# 612_jetracer_esp32s3_030008.net
KiCad netlist of a schematic drawn in EAGLE
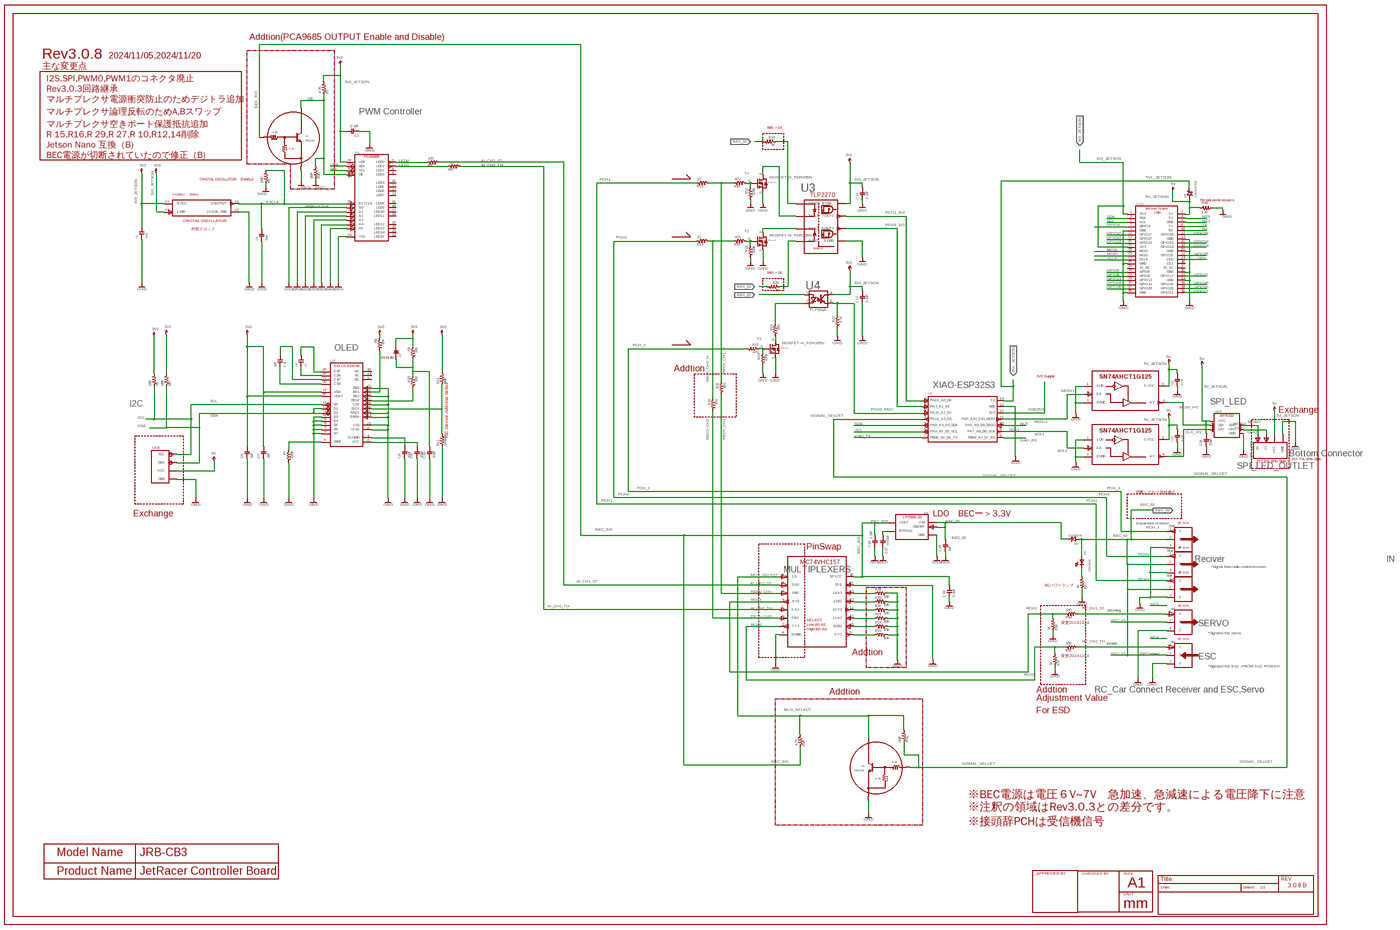
[diagram p0: schematic, sheet 1, overview]
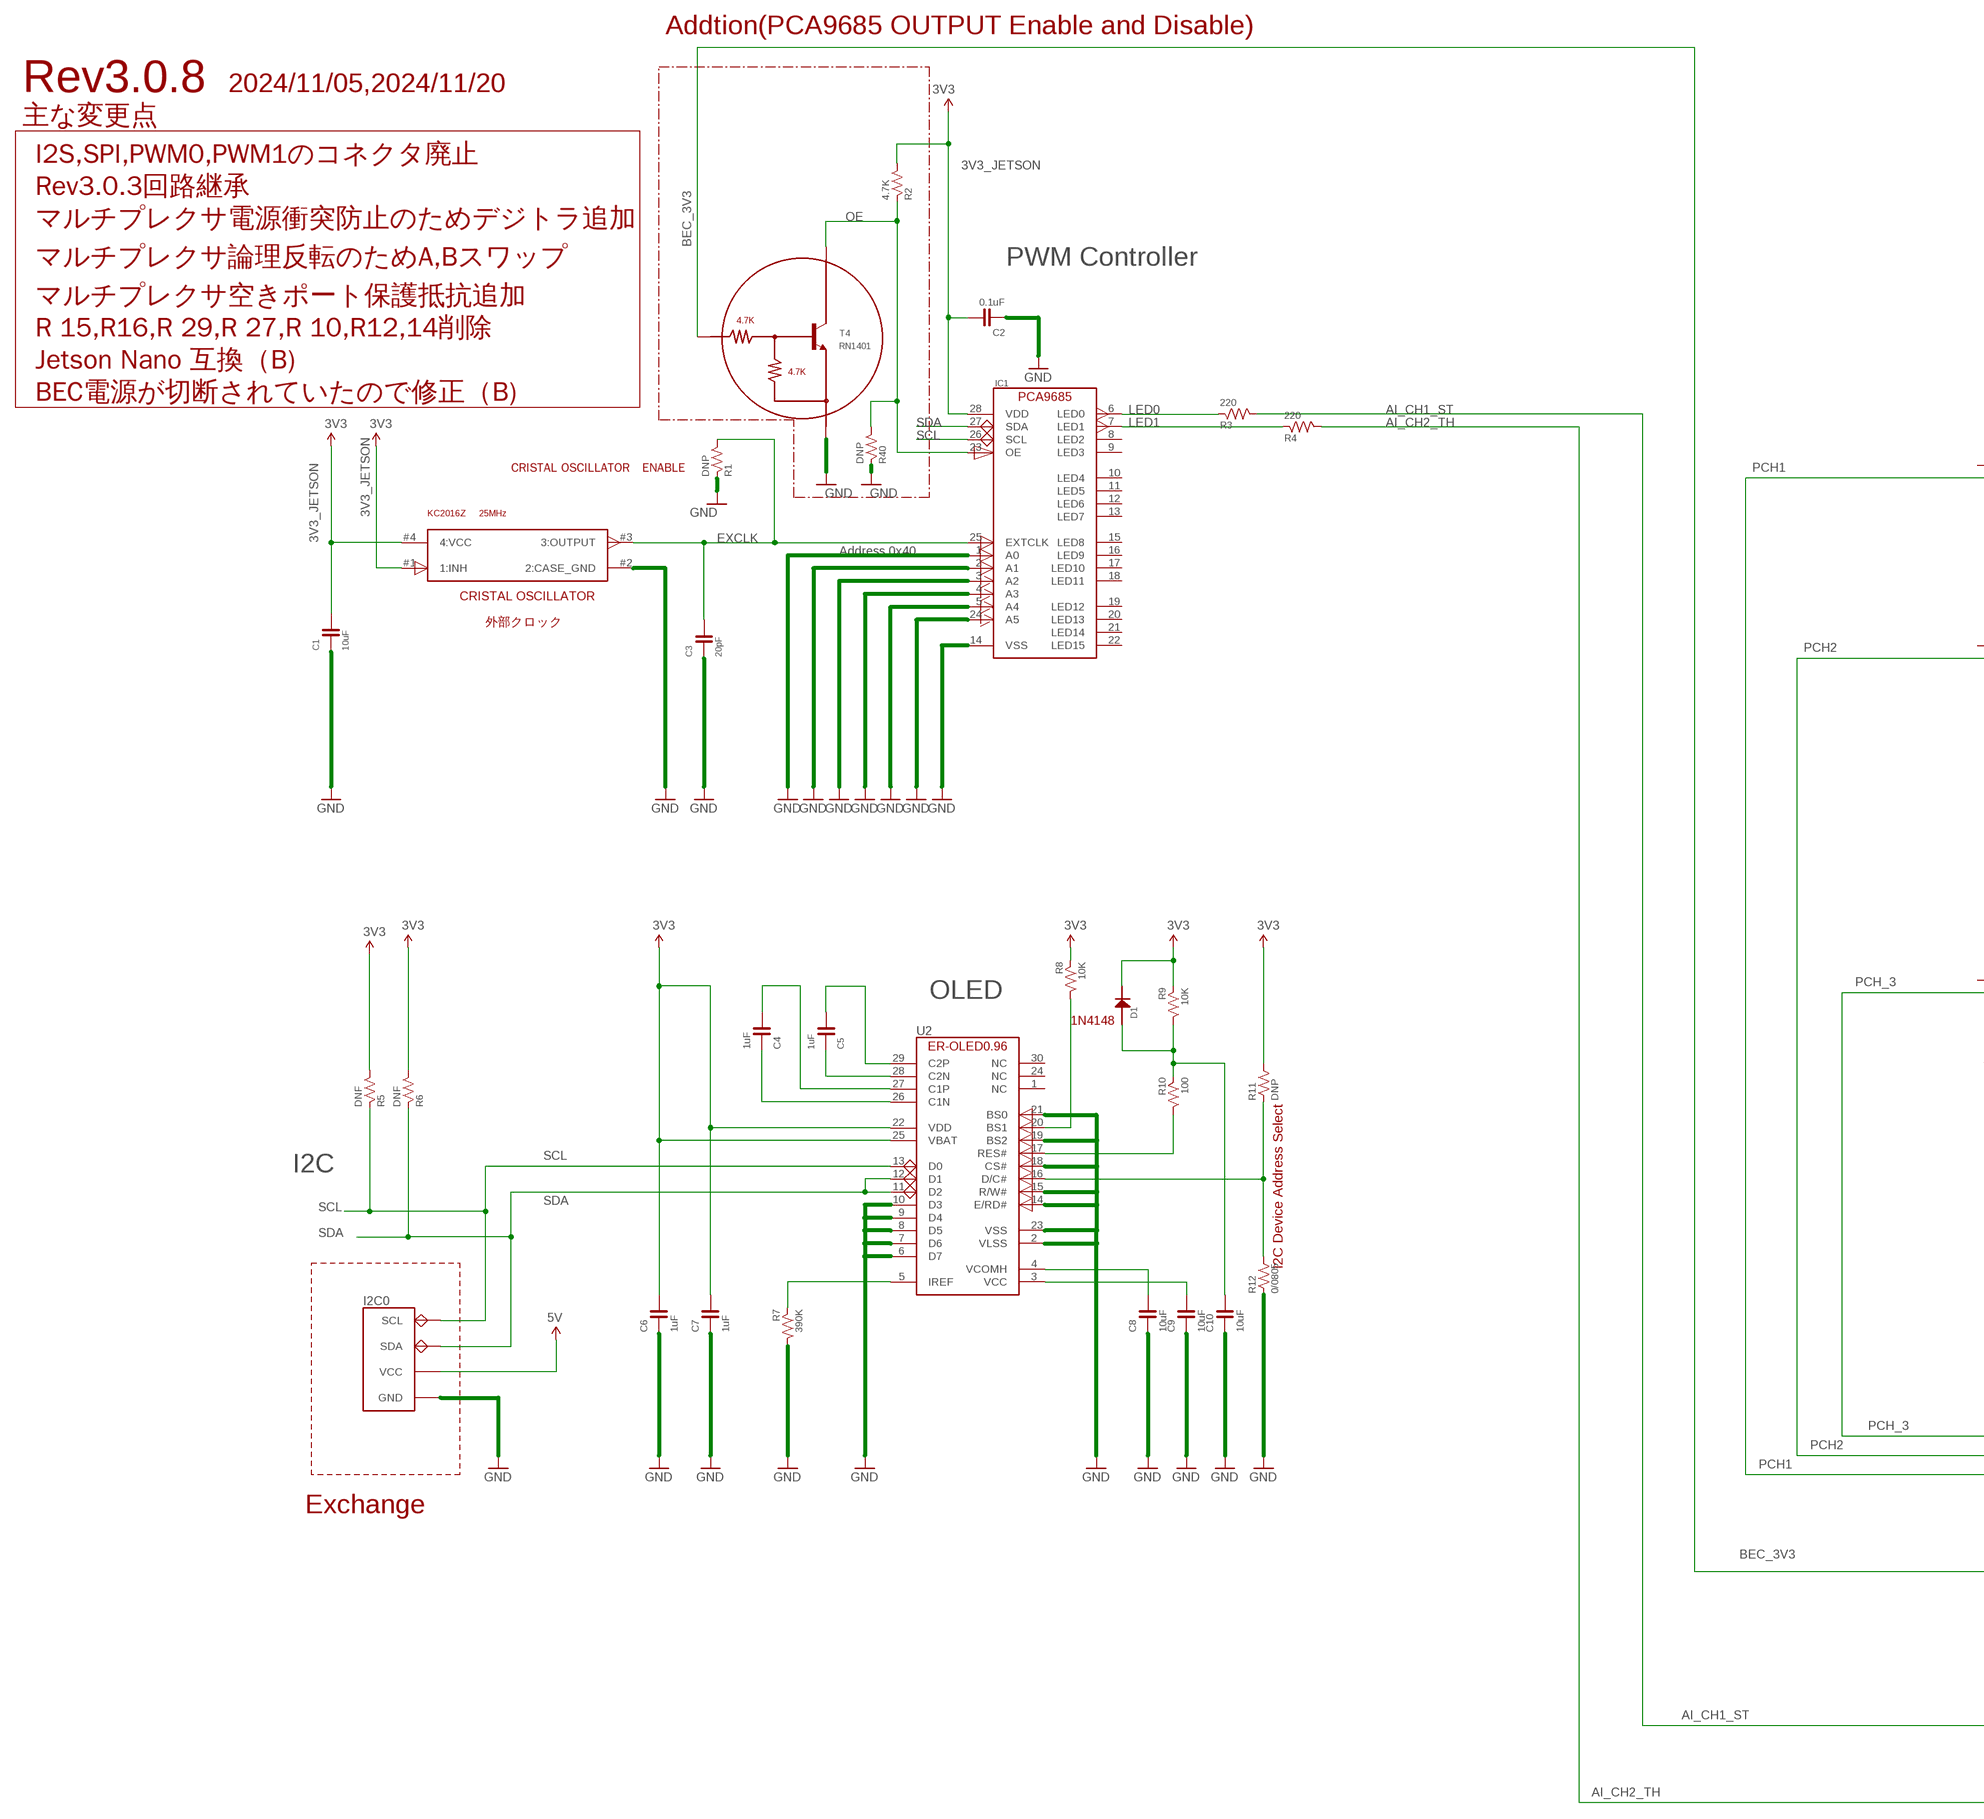
[diagram p1: schematic, sheet 1, part 1 of 4]
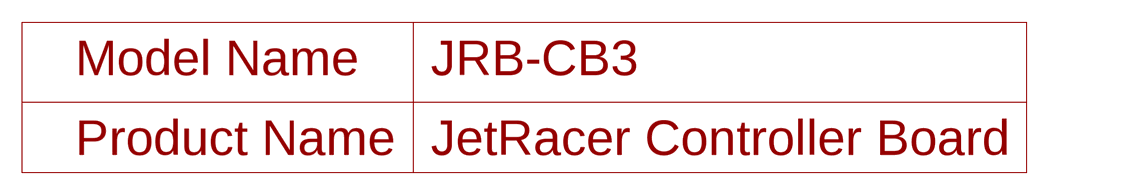
[diagram p2: schematic, sheet 1, part 2 of 4]
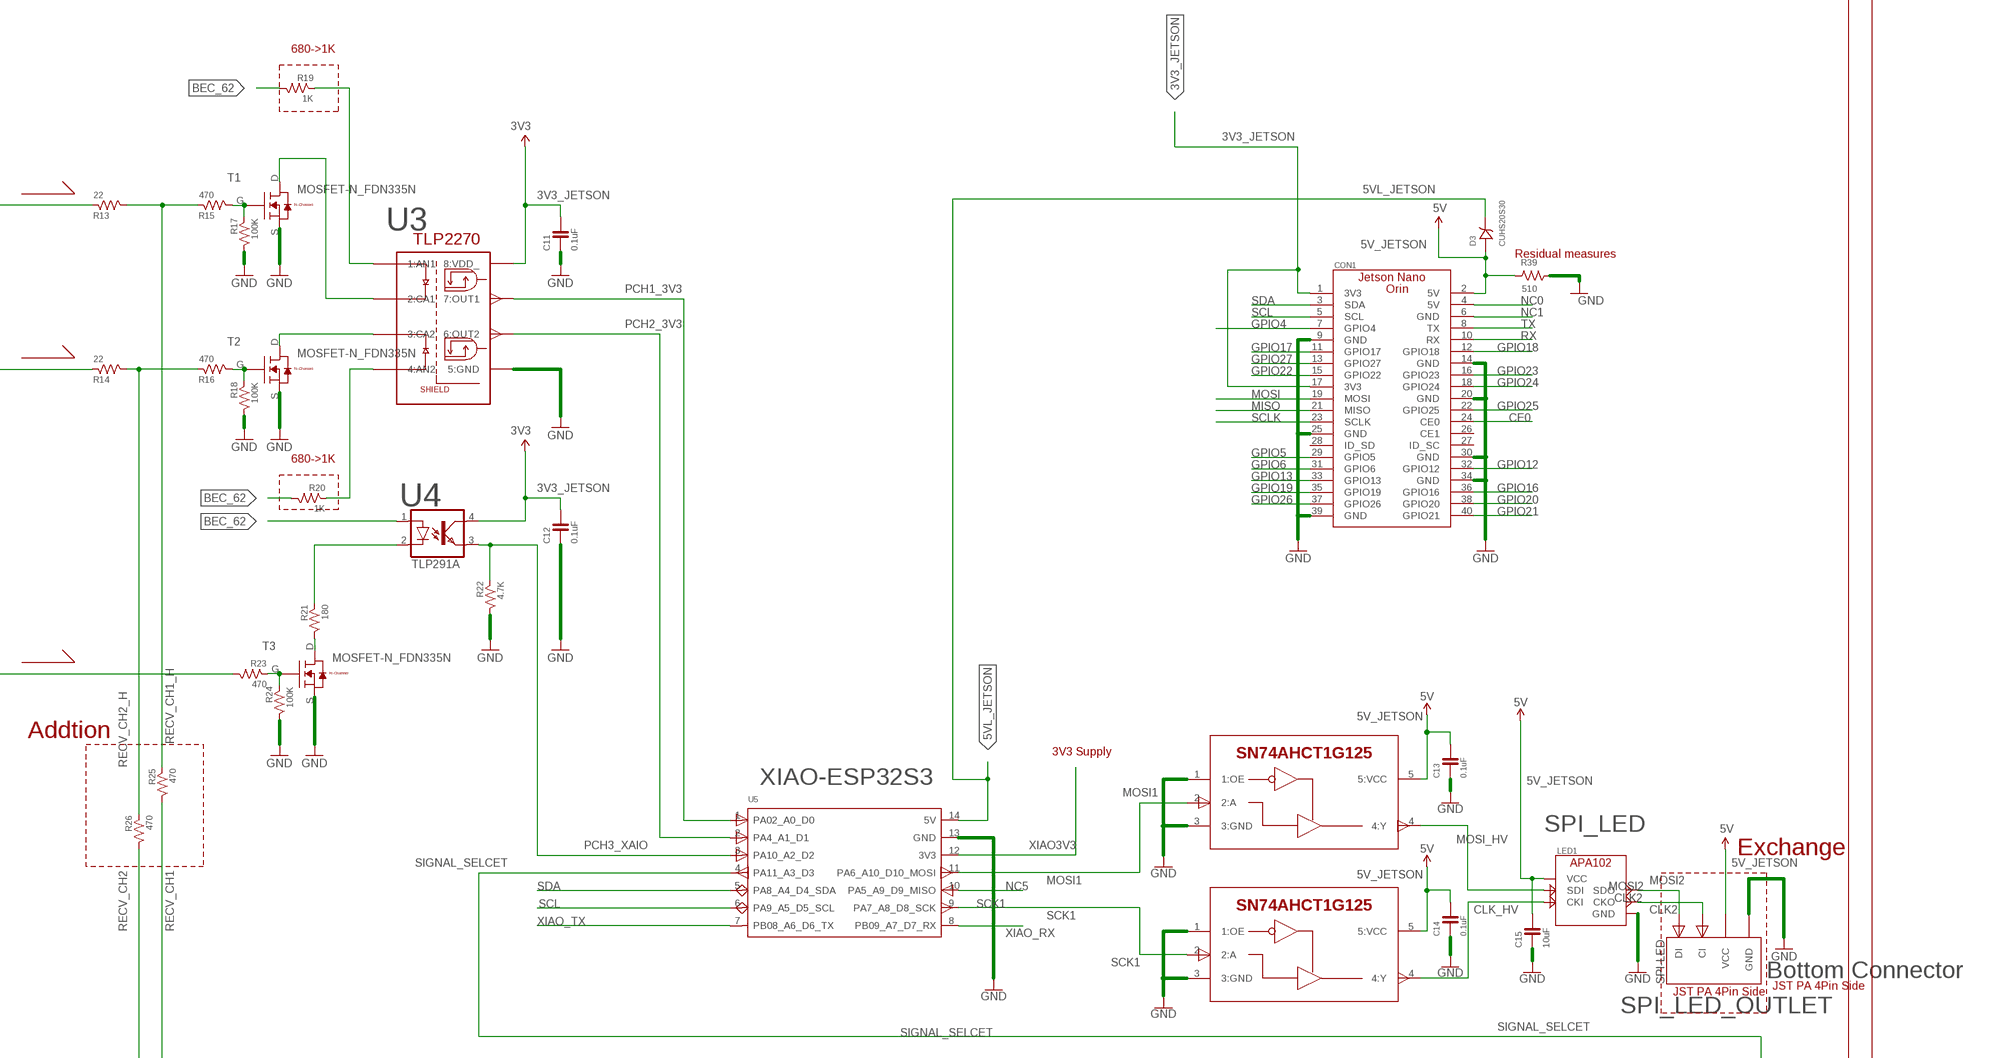
[diagram p3: schematic, sheet 1, part 3 of 4]
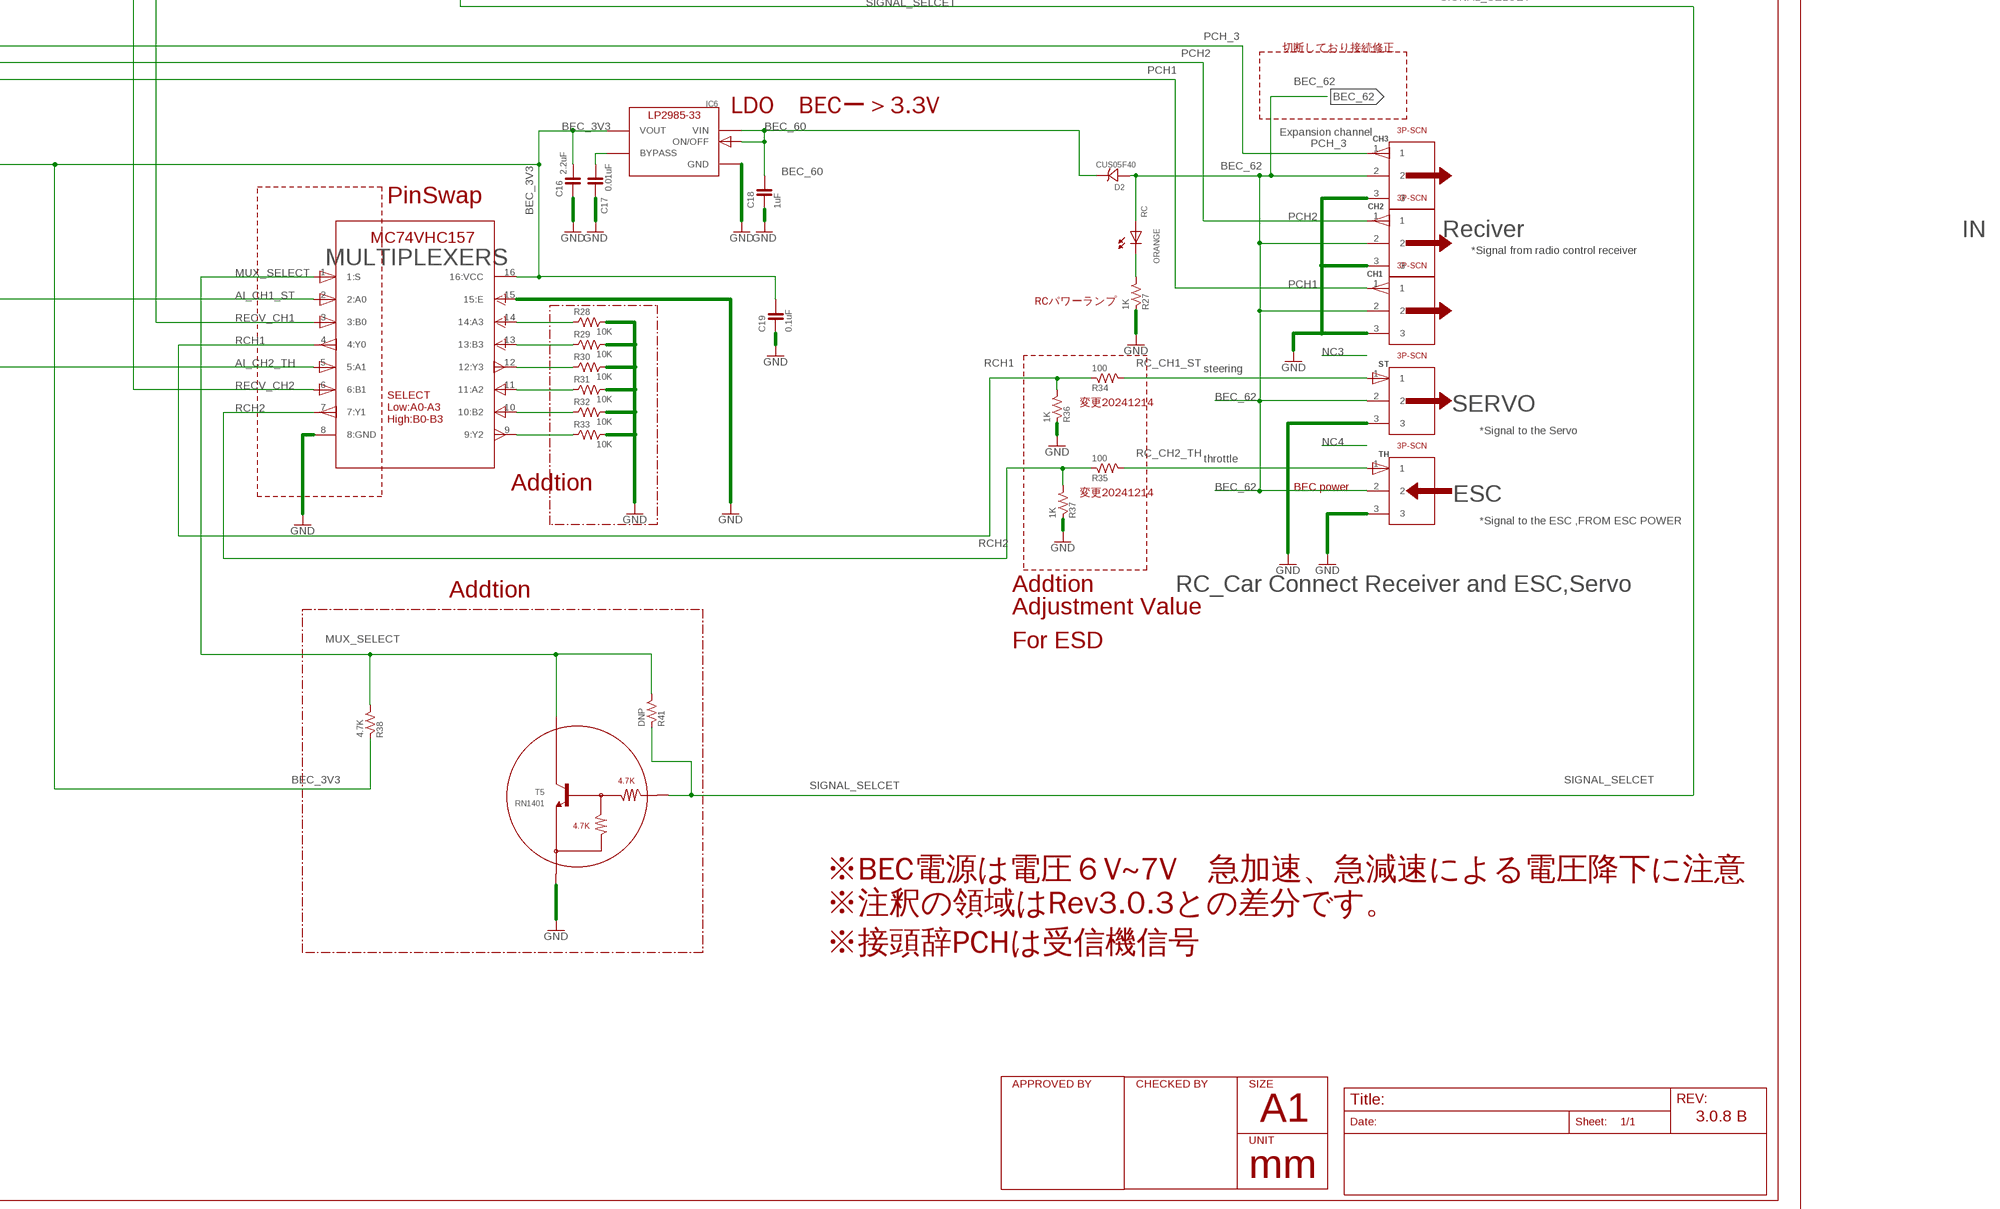
[diagram p4: schematic, sheet 1, part 4 of 4]

(export (version "E")
  (design (tool "Eeschema 10.0.6"))
  (components
    (comp (ref "C1")
      (value "10uF")
      (footprint "eagle-import:0402")
      (libsource (lib "eagle-import") (part "CAPACITOR-0402"))
    )
    (comp (ref "C2")
      (value "0.1uF")
      (footprint "eagle-import:0603")
      (libsource (lib "eagle-import") (part "CAPACITOR-0603"))
    )
    (comp (ref "C3")
      (value "20pF")
      (footprint "eagle-import:0402")
      (libsource (lib "eagle-import") (part "CAPACITOR-0402"))
    )
    (comp (ref "C4")
      (value "1uF")
      (footprint "eagle-import:0603")
      (libsource (lib "eagle-import") (part "CAPACITOR-0603"))
    )
    (comp (ref "C5")
      (value "1uF")
      (footprint "eagle-import:0603")
      (libsource (lib "eagle-import") (part "CAPACITOR-0603"))
    )
    (comp (ref "C6")
      (value "1uF")
      (footprint "eagle-import:0603")
      (libsource (lib "eagle-import") (part "CAPACITOR-0603"))
    )
    (comp (ref "C7")
      (value "1uF")
      (footprint "eagle-import:0603")
      (libsource (lib "eagle-import") (part "CAPACITOR-0603"))
    )
    (comp (ref "C8")
      (value "10uF")
      (footprint "eagle-import:0603")
      (libsource (lib "eagle-import") (part "CAPACITOR-0603"))
    )
    (comp (ref "C9")
      (value "10uF")
      (footprint "eagle-import:0603")
      (libsource (lib "eagle-import") (part "CAPACITOR-0603"))
    )
    (comp (ref "C10")
      (value "10uF")
      (footprint "eagle-import:0603")
      (libsource (lib "eagle-import") (part "CAPACITOR-0603"))
    )
    (comp (ref "C11")
      (value "0.1uF")
      (footprint "eagle-import:0603")
      (libsource (lib "eagle-import") (part "CAPACITOR-0603"))
    )
    (comp (ref "C12")
      (value "0.1uF")
      (footprint "eagle-import:0603")
      (libsource (lib "eagle-import") (part "CAPACITOR-0603"))
    )
    (comp (ref "C13")
      (value "0.1uF")
      (footprint "eagle-import:0402")
      (libsource (lib "eagle-import") (part "CAPACITOR-0402"))
    )
    (comp (ref "C14")
      (value "0.1uF")
      (footprint "eagle-import:0402")
      (libsource (lib "eagle-import") (part "CAPACITOR-0402"))
    )
    (comp (ref "C15")
      (value "10uF")
      (footprint "eagle-import:0603")
      (libsource (lib "eagle-import") (part "CAPACITOR-0603"))
    )
    (comp (ref "C16")
      (value "2.2uF")
      (footprint "eagle-import:0603")
      (libsource (lib "eagle-import") (part "CAPACITOR-0603"))
    )
    (comp (ref "C17")
      (value "0.01uF")
      (footprint "eagle-import:0603")
      (libsource (lib "eagle-import") (part "CAPACITOR-0603"))
    )
    (comp (ref "C18")
      (value "1uF")
      (footprint "eagle-import:0603")
      (libsource (lib "eagle-import") (part "CAPACITOR-0603"))
    )
    (comp (ref "C19")
      (value "0.1uF")
      (footprint "eagle-import:0603")
      (libsource (lib "eagle-import") (part "CAPACITOR-0603"))
    )
    (comp (ref "CH1")
      (value "3P-SCN")
      (footprint "eagle-import:3P-SCN")
      (libsource (lib "eagle-import") (part "3P-SCN"))
    )
    (comp (ref "CH2")
      (value "3P-SCN")
      (footprint "eagle-import:3P-SCN")
      (libsource (lib "eagle-import") (part "3P-SCN"))
    )
    (comp (ref "CH3")
      (value "3P-SCN")
      (footprint "eagle-import:3P-SCN")
      (libsource (lib "eagle-import") (part "3P-SCN"))
    )
    (comp (ref "CON1")
      (value "JETSON_NANOJETSON_ORIN_NANO")
      (footprint "eagle-import:JETSON_ORIN_NANO_DIMENTION")
      (libsource (lib "eagle-import") (part "JETSON_NANOJETSON_ORIN_NANO"))
    )
    (comp (ref "D1")
      (value "1N4148")
      (footprint "eagle-import:1N4148W")
      (libsource (lib "eagle-import") (part "1N4148"))
    )
    (comp (ref "D2")
      (value "CUS05F40")
      (footprint "eagle-import:CUS05F40")
      (libsource (lib "eagle-import") (part "CUS05F40"))
    )
    (comp (ref "D3")
      (value "CUHS20S30")
      (footprint "eagle-import:US2H")
      (libsource (lib "eagle-import") (part "CUHS20S30"))
    )
    (comp (ref "I2C0")
      (value "FABO_BRICK_I2C-B04B-PASK-1")
      (footprint "eagle-import:FABO_BRICK_I2C_B04B-PASK-1")
      (libsource (lib "eagle-import") (part "FABO_BRICK_I2C-B04B-PASK-1"))
    )
    (comp (ref "IC1")
      (value "PCA9685PW,BS")
      (footprint "eagle-import:PCA9685")
      (libsource (lib "eagle-import") (part "PCA9685PW,BS"))
    )
    (comp (ref "IC3")
      (value "SN74AHCT1G125")
      (footprint "eagle-import:SOT-1DOT1")
      (libsource (lib "eagle-import") (part "SN74AHCT1G125"))
    )
    (comp (ref "IC4")
      (value "SN74AHCT1G125")
      (footprint "eagle-import:SOT-1DOT1")
      (libsource (lib "eagle-import") (part "SN74AHCT1G125"))
    )
    (comp (ref "IC5")
      (value "MC74VHC157")
      (footprint "eagle-import:MC74VHC157_TSSOP-16")
      (libsource (lib "eagle-import") (part "MC74VHC157"))
    )
    (comp (ref "IC6")
      (value "LP2985-33DBVR")
      (footprint "eagle-import:SOT-23-5")
      (libsource (lib "eagle-import") (part "LP2985-33DBVR"))
    )
    (comp (ref "LED1")
      (value "APA102_IPIXEL")
      (footprint "eagle-import:APA102_2020")
      (libsource (lib "eagle-import") (part "APA102_IPIXEL"))
    )
    (comp (ref "R1")
      (value "DNP")
      (footprint "eagle-import:0603")
      (libsource (lib "eagle-import") (part "RESISTOR-0603"))
    )
    (comp (ref "R2")
      (value "4.7K")
      (footprint "eagle-import:0603")
      (libsource (lib "eagle-import") (part "RESISTOR-0603"))
    )
    (comp (ref "R3")
      (value "220")
      (footprint "eagle-import:0603")
      (libsource (lib "eagle-import") (part "RESISTOR-0603"))
    )
    (comp (ref "R4")
      (value "220")
      (footprint "eagle-import:0603")
      (libsource (lib "eagle-import") (part "RESISTOR-0603"))
    )
    (comp (ref "R5")
      (value "DNF")
      (footprint "eagle-import:0603")
      (libsource (lib "eagle-import") (part "RESISTOR-0603"))
    )
    (comp (ref "R6")
      (value "DNF")
      (footprint "eagle-import:0603")
      (libsource (lib "eagle-import") (part "RESISTOR-0603"))
    )
    (comp (ref "R7")
      (value "390K")
      (footprint "eagle-import:0603")
      (libsource (lib "eagle-import") (part "RESISTOR-0603"))
    )
    (comp (ref "R8")
      (value "10K")
      (footprint "eagle-import:0603")
      (libsource (lib "eagle-import") (part "RESISTOR-0603"))
    )
    (comp (ref "R9")
      (value "10K")
      (footprint "eagle-import:0603")
      (libsource (lib "eagle-import") (part "RESISTOR-0603"))
    )
    (comp (ref "R10")
      (value "100")
      (footprint "eagle-import:0603")
      (libsource (lib "eagle-import") (part "RESISTOR-0603"))
    )
    (comp (ref "R11")
      (value "DNP")
      (footprint "eagle-import:0805")
      (fields (field (name "SPICEPREFIX") "R"))
      (libsource (lib "eagle-import") (part "RESISTOR-0805"))
    )
    (comp (ref "R12")
      (value "0/0805")
      (footprint "eagle-import:0805")
      (libsource (lib "eagle-import") (part "RESISTOR-0805"))
    )
    (comp (ref "R13")
      (value "22")
      (footprint "eagle-import:0603")
      (libsource (lib "eagle-import") (part "RESISTOR-0603"))
    )
    (comp (ref "R14")
      (value "22")
      (footprint "eagle-import:0603")
      (fields (field (name "SPICEPREFIX") "R"))
      (libsource (lib "eagle-import") (part "RESISTOR-0603"))
    )
    (comp (ref "R15")
      (value "470")
      (footprint "eagle-import:0603")
      (libsource (lib "eagle-import") (part "RESISTOR-0603"))
    )
    (comp (ref "R16")
      (value "470")
      (footprint "eagle-import:0603")
      (libsource (lib "eagle-import") (part "RESISTOR-0603"))
    )
    (comp (ref "R17")
      (value "100K")
      (footprint "eagle-import:0603")
      (libsource (lib "eagle-import") (part "RESISTOR-0603"))
    )
    (comp (ref "R18")
      (value "100K")
      (footprint "eagle-import:0603")
      (libsource (lib "eagle-import") (part "RESISTOR-0603"))
    )
    (comp (ref "R19")
      (value "1K")
      (footprint "eagle-import:0603")
      (libsource (lib "eagle-import") (part "RESISTOR-0603"))
    )
    (comp (ref "R20")
      (value "1K")
      (footprint "eagle-import:0603")
      (libsource (lib "eagle-import") (part "RESISTOR-0603"))
    )
    (comp (ref "R21")
      (value "180")
      (footprint "eagle-import:0603")
      (libsource (lib "eagle-import") (part "RESISTOR-0603"))
    )
    (comp (ref "R22")
      (value "4.7K")
      (footprint "eagle-import:0603")
      (libsource (lib "eagle-import") (part "RESISTOR-0603"))
    )
    (comp (ref "R23")
      (value "470")
      (footprint "eagle-import:0603")
      (libsource (lib "eagle-import") (part "RESISTOR-0603"))
    )
    (comp (ref "R24")
      (value "100K")
      (footprint "eagle-import:0603")
      (libsource (lib "eagle-import") (part "RESISTOR-0603"))
    )
    (comp (ref "R25")
      (value "470")
      (footprint "eagle-import:0603")
      (libsource (lib "eagle-import") (part "RESISTOR-0603"))
    )
    (comp (ref "R26")
      (value "470")
      (footprint "eagle-import:0603")
      (libsource (lib "eagle-import") (part "RESISTOR-0603"))
    )
    (comp (ref "R27")
      (value "1K")
      (footprint "eagle-import:0603")
      (libsource (lib "eagle-import") (part "RESISTOR-0603"))
    )
    (comp (ref "R28")
      (value "10K")
      (footprint "eagle-import:0402")
      (fields (field (name "SPICEPREFIX") "R"))
      (libsource (lib "eagle-import") (part "RESISTOR-0402"))
    )
    (comp (ref "R29")
      (value "10K")
      (footprint "eagle-import:0402")
      (libsource (lib "eagle-import") (part "RESISTOR-0402"))
    )
    (comp (ref "R30")
      (value "10K")
      (footprint "eagle-import:0402")
      (fields (field (name "SPICEPREFIX") "R"))
      (libsource (lib "eagle-import") (part "RESISTOR-0402"))
    )
    (comp (ref "R31")
      (value "10K")
      (footprint "eagle-import:0402")
      (libsource (lib "eagle-import") (part "RESISTOR-0402"))
    )
    (comp (ref "R32")
      (value "10K")
      (footprint "eagle-import:0402")
      (libsource (lib "eagle-import") (part "RESISTOR-0402"))
    )
    (comp (ref "R33")
      (value "10K")
      (footprint "eagle-import:0402")
      (libsource (lib "eagle-import") (part "RESISTOR-0402"))
    )
    (comp (ref "R34")
      (value "100")
      (footprint "eagle-import:0603")
      (libsource (lib "eagle-import") (part "RESISTOR-0603"))
    )
    (comp (ref "R35")
      (value "100")
      (footprint "eagle-import:0603")
      (libsource (lib "eagle-import") (part "RESISTOR-0603"))
    )
    (comp (ref "R36")
      (value "1K")
      (footprint "eagle-import:0603")
      (libsource (lib "eagle-import") (part "RESISTOR-0603"))
    )
    (comp (ref "R37")
      (value "1K")
      (footprint "eagle-import:0603")
      (libsource (lib "eagle-import") (part "RESISTOR-0603"))
    )
    (comp (ref "R38")
      (value "4.7K")
      (footprint "eagle-import:0603")
      (libsource (lib "eagle-import") (part "RESISTOR-0603"))
    )
    (comp (ref "R39")
      (value "510")
      (footprint "eagle-import:0805")
      (libsource (lib "eagle-import") (part "RESISTOR-0805"))
    )
    (comp (ref "R40")
      (value "DNP")
      (footprint "eagle-import:0603")
      (libsource (lib "eagle-import") (part "RESISTOR-0603"))
    )
    (comp (ref "R41")
      (value "DNP")
      (footprint "eagle-import:0603")
      (libsource (lib "eagle-import") (part "RESISTOR-0603"))
    )
    (comp (ref "RC")
      (value "ORANGE")
      (footprint "eagle-import:0603")
      (libsource (lib "eagle-import") (part "LED-0603"))
    )
    (comp (ref "SPI-LED")
      (value "FABO-SPI-LED-B04B")
      (footprint "eagle-import:SPI-B04B-PASK-1")
      (libsource (lib "eagle-import") (part "FABO-SPI-LED-B04B"))
    )
    (comp (ref "ST")
      (value "3P-SCN")
      (footprint "eagle-import:3P-SCN")
      (libsource (lib "eagle-import") (part "3P-SCN"))
    )
    (comp (ref "T1")
      (value "MOSFET-N_FDN335N")
      (footprint "eagle-import:SUPERSOT-3")
      (libsource (lib "eagle-import") (part "MOSFET-N_FDN335N"))
    )
    (comp (ref "T2")
      (value "MOSFET-N_FDN335N")
      (footprint "eagle-import:SUPERSOT-3")
      (libsource (lib "eagle-import") (part "MOSFET-N_FDN335N"))
    )
    (comp (ref "T3")
      (value "MOSFET-N_FDN335N")
      (footprint "eagle-import:SUPERSOT-3")
      (libsource (lib "eagle-import") (part "MOSFET-N_FDN335N"))
    )
    (comp (ref "T4")
      (value "RN1401")
      (footprint "eagle-import:SC-59")
      (libsource (lib "eagle-import") (part "RN1401"))
    )
    (comp (ref "T5")
      (value "RN1401")
      (footprint "eagle-import:SC-59")
      (libsource (lib "eagle-import") (part "RN1401"))
    )
    (comp (ref "TH")
      (value "3P-SCN")
      (footprint "eagle-import:3P-SCN")
      (libsource (lib "eagle-import") (part "3P-SCN"))
    )
    (comp (ref "U1")
      (value "KC2016Z")
      (footprint "eagle-import:KC2016Z")
      (fields (field (name "SPICEPREFIX") "E"))
      (libsource (lib "eagle-import") (part "KC2016Z"))
    )
    (comp (ref "U2")
      (value "ER-OLED0.96-1ER-CON30HT-1")
      (footprint "eagle-import:ER-CON30HT-1")
      (libsource (lib "eagle-import") (part "ER-OLED0.96-1ER-CON30HT-1"))
    )
    (comp (ref "U3")
      (value "TLP2270")
      (footprint "eagle-import:TLP2270")
      (libsource (lib "eagle-import") (part "TLP2270"))
    )
    (comp (ref "U4")
      (value "TLP291A")
      (footprint "eagle-import:11-3C1")
      (libsource (lib "eagle-import") (part "TLP291A"))
    )
    (comp (ref "U5")
      (value "MOUDLE-SEEEDUINO-XIAO-ESP32C3SINGLESIDE")
      (footprint "eagle-import:MOUDLE14P-DIP_SINGLE")
      (libsource (lib "eagle-import") (part "MOUDLE-SEEEDUINO-XIAO-ESP32C3SINGLESIDE"))
    )
  )
  (nets
    (net (code "1") (name "/AI_CH1_ST") (class "Default")
      (node (ref "IC5") (pin "2") (pinfunction "2:A0_2") (pintype "bidirectional"))
      (node (ref "R3") (pin "2") (pinfunction "2_2") (pintype "bidirectional"))
    )
    (net (code "2") (name "/AI_CH2_TH") (class "Default")
      (node (ref "IC5") (pin "5") (pinfunction "5:A1_5") (pintype "bidirectional"))
      (node (ref "R4") (pin "2") (pinfunction "2_2") (pintype "bidirectional"))
    )
    (net (code "3") (name "/BEC_3V3") (class "Default")
      (node (ref "C16") (pin "2") (pinfunction "2_2") (pintype "passive"))
      (node (ref "C19") (pin "2") (pinfunction "2_2") (pintype "passive"))
      (node (ref "IC5") (pin "16") (pinfunction "16:VCC_16") (pintype "bidirectional"))
      (node (ref "IC6") (pin "5") (pinfunction "VOUT_5") (pintype "output"))
      (node (ref "R38") (pin "1") (pinfunction "1_1") (pintype "bidirectional"))
      (node (ref "T4") (pin "B") (pinfunction "B_B") (pintype "passive"))
    )
    (net (code "4") (name "/BEC_60") (class "Default")
      (node (ref "C18") (pin "2") (pinfunction "2_2") (pintype "passive"))
      (node (ref "D2") (pin "C") (pinfunction "CATHODE_C") (pintype "bidirectional"))
      (node (ref "IC6") (pin "1") (pinfunction "VIN_1") (pintype "input"))
      (node (ref "IC6") (pin "3") (pinfunction "ON/OFF_3") (pintype "input"))
    )
    (net (code "5") (name "/CE0") (class "Default")
      (node (ref "CON1") (pin "24") (pinfunction "CE0_24") (pintype "bidirectional"))
    )
    (net (code "6") (name "/CLK2") (class "Default")
      (node (ref "LED1") (pin "CKO") (pinfunction "CKO_CKO") (pintype "bidirectional"))
      (node (ref "SPI-LED") (pin "CI") (pinfunction "CI_CI") (pintype "bidirectional"))
    )
    (net (code "7") (name "/CLK_HV") (class "Default")
      (node (ref "IC4") (pin "4") (pinfunction "4:Y_4") (pintype "output"))
      (node (ref "LED1") (pin "CKI") (pinfunction "CKI_CKI") (pintype "bidirectional"))
    )
    (net (code "8") (name "/EXCLK") (class "Default")
      (node (ref "C3") (pin "2") (pinfunction "2_2") (pintype "passive"))
      (node (ref "IC1") (pin "25") (pinfunction "EXTCLK_25") (pintype "bidirectional"))
      (node (ref "R1") (pin "2") (pinfunction "2_2") (pintype "bidirectional"))
      (node (ref "U1") (pin "#3") (pinfunction "3:OUTPUT_#3") (pintype "bidirectional"))
    )
    (net (code "9") (name "/GPIO4") (class "Default")
      (node (ref "CON1") (pin "7") (pinfunction "GPIO4_7") (pintype "bidirectional"))
    )
    (net (code "10") (name "/GPIO5") (class "Default")
      (node (ref "CON1") (pin "29") (pinfunction "GPIO5_29") (pintype "bidirectional"))
    )
    (net (code "11") (name "/GPIO6") (class "Default")
      (node (ref "CON1") (pin "31") (pinfunction "GPIO6_31") (pintype "bidirectional"))
    )
    (net (code "12") (name "/GPIO12") (class "Default")
      (node (ref "CON1") (pin "32") (pinfunction "GPIO12_32") (pintype "bidirectional"))
    )
    (net (code "13") (name "/GPIO13") (class "Default")
      (node (ref "CON1") (pin "33") (pinfunction "GPIO13_33") (pintype "bidirectional"))
    )
    (net (code "14") (name "/GPIO16") (class "Default")
      (node (ref "CON1") (pin "36") (pinfunction "GPIO16_36") (pintype "bidirectional"))
    )
    (net (code "15") (name "/GPIO17") (class "Default")
      (node (ref "CON1") (pin "11") (pinfunction "GPIO17_11") (pintype "bidirectional"))
    )
    (net (code "16") (name "/GPIO18") (class "Default")
      (node (ref "CON1") (pin "12") (pinfunction "GPIO18_12") (pintype "bidirectional"))
    )
    (net (code "17") (name "/GPIO19") (class "Default")
      (node (ref "CON1") (pin "35") (pinfunction "GPIO19_35") (pintype "bidirectional"))
    )
    (net (code "18") (name "/GPIO20") (class "Default")
      (node (ref "CON1") (pin "38") (pinfunction "GPIO20_38") (pintype "bidirectional"))
    )
    (net (code "19") (name "/GPIO21") (class "Default")
      (node (ref "CON1") (pin "40") (pinfunction "GPIO21_40") (pintype "bidirectional"))
    )
    (net (code "20") (name "/GPIO22") (class "Default")
      (node (ref "CON1") (pin "15") (pinfunction "GPIO22_15") (pintype "bidirectional"))
    )
    (net (code "21") (name "/GPIO23") (class "Default")
      (node (ref "CON1") (pin "16") (pinfunction "GPIO23_16") (pintype "bidirectional"))
    )
    (net (code "22") (name "/GPIO24") (class "Default")
      (node (ref "CON1") (pin "18") (pinfunction "GPIO24_18") (pintype "bidirectional"))
    )
    (net (code "23") (name "/GPIO25") (class "Default")
      (node (ref "CON1") (pin "22") (pinfunction "GPIO25_22") (pintype "bidirectional"))
    )
    (net (code "24") (name "/GPIO26") (class "Default")
      (node (ref "CON1") (pin "37") (pinfunction "GPIO26_37") (pintype "bidirectional"))
    )
    (net (code "25") (name "/GPIO27") (class "Default")
      (node (ref "CON1") (pin "13") (pinfunction "GPIO27_13") (pintype "bidirectional"))
    )
    (net (code "26") (name "/LED0") (class "Default")
      (node (ref "IC1") (pin "6") (pinfunction "LED0_6") (pintype "bidirectional"))
      (node (ref "R3") (pin "1") (pinfunction "1_1") (pintype "bidirectional"))
    )
    (net (code "27") (name "/LED1") (class "Default")
      (node (ref "IC1") (pin "7") (pinfunction "LED1_7") (pintype "bidirectional"))
      (node (ref "R4") (pin "1") (pinfunction "1_1") (pintype "bidirectional"))
    )
    (net (code "28") (name "/MISO") (class "Default")
      (node (ref "CON1") (pin "21") (pinfunction "MISO_21") (pintype "bidirectional"))
    )
    (net (code "29") (name "/MOSI") (class "Default")
      (node (ref "CON1") (pin "19") (pinfunction "MOSI_19") (pintype "bidirectional"))
    )
    (net (code "30") (name "/MOSI1") (class "Default")
      (node (ref "IC3") (pin "2") (pinfunction "2:A_2") (pintype "input"))
      (node (ref "U5") (pin "11") (pinfunction "PA6_A10_D10_MOSI_11") (pintype "bidirectional"))
    )
    (net (code "31") (name "/MOSI2") (class "Default")
      (node (ref "LED1") (pin "SDO") (pinfunction "SDO_SDO") (pintype "bidirectional"))
      (node (ref "SPI-LED") (pin "DI") (pinfunction "DI_DI") (pintype "bidirectional"))
    )
    (net (code "32") (name "/MOSI_HV") (class "Default")
      (node (ref "IC3") (pin "4") (pinfunction "4:Y_4") (pintype "output"))
      (node (ref "LED1") (pin "SDI") (pinfunction "SDI_SDI") (pintype "bidirectional"))
    )
    (net (code "33") (name "/MUX_SELECT") (class "Default")
      (node (ref "IC5") (pin "1") (pinfunction "1:S_1") (pintype "bidirectional"))
      (node (ref "R38") (pin "2") (pinfunction "2_2") (pintype "bidirectional"))
      (node (ref "R41") (pin "2") (pinfunction "2_2") (pintype "bidirectional"))
      (node (ref "T5") (pin "C") (pinfunction "C_C") (pintype "passive"))
    )
    (net (code "34") (name "/NC0") (class "Default")
      (node (ref "CON1") (pin "4") (pinfunction "5V_4") (pintype "bidirectional"))
    )
    (net (code "35") (name "/NC1") (class "Default")
      (node (ref "CON1") (pin "6") (pinfunction "GND_6") (pintype "bidirectional"))
    )
    (net (code "38") (name "/NC5") (class "Default")
      (node (ref "U5") (pin "10") (pinfunction "PA5_A9_D9_MISO_10") (pintype "bidirectional"))
    )
    (net (code "39") (name "/OE") (class "Default")
      (node (ref "IC1") (pin "23") (pinfunction "OE_23") (pintype "bidirectional"))
      (node (ref "R2") (pin "1") (pinfunction "1_1") (pintype "bidirectional"))
      (node (ref "R40") (pin "2") (pinfunction "2_2") (pintype "bidirectional"))
      (node (ref "T4") (pin "C") (pinfunction "C_C") (pintype "passive"))
    )
    (net (code "40") (name "/PCH1") (class "Default")
      (node (ref "CH1") (pin "1") (pinfunction "1_1") (pintype "bidirectional"))
      (node (ref "R13") (pin "1") (pinfunction "1_1") (pintype "bidirectional"))
    )
    (net (code "41") (name "/PCH1_3V3") (class "Default")
      (node (ref "U3") (pin "7") (pinfunction "7:OUT1_7") (pintype "bidirectional"))
      (node (ref "U5") (pin "1") (pinfunction "PA02_A0_D0_1") (pintype "bidirectional"))
    )
    (net (code "42") (name "/PCH2") (class "Default")
      (node (ref "CH2") (pin "1") (pinfunction "1_1") (pintype "bidirectional"))
      (node (ref "R14") (pin "1") (pinfunction "1_1") (pintype "bidirectional"))
    )
    (net (code "43") (name "/PCH2_3V3") (class "Default")
      (node (ref "U3") (pin "6") (pinfunction "6:OUT2_6") (pintype "bidirectional"))
      (node (ref "U5") (pin "2") (pinfunction "PA4_A1_D1_2") (pintype "bidirectional"))
    )
    (net (code "44") (name "/PCH3_XAIO") (class "Default")
      (node (ref "R22") (pin "1") (pinfunction "1_1") (pintype "bidirectional"))
      (node (ref "U4") (pin "3") (pinfunction "EMI_3") (pintype "passive"))
      (node (ref "U5") (pin "3") (pinfunction "PA10_A2_D2_3") (pintype "bidirectional"))
    )
    (net (code "45") (name "/PCH_3") (class "Default")
      (node (ref "CH3") (pin "1") (pinfunction "1_1") (pintype "bidirectional"))
      (node (ref "R23") (pin "2") (pinfunction "2_2") (pintype "bidirectional"))
    )
    (net (code "46") (name "/RCH1") (class "Default")
      (node (ref "IC5") (pin "4") (pinfunction "4:Y0_4") (pintype "bidirectional"))
      (node (ref "R34") (pin "1") (pinfunction "1_1") (pintype "bidirectional"))
      (node (ref "R36") (pin "2") (pinfunction "2_2") (pintype "bidirectional"))
    )
    (net (code "47") (name "/RCH2") (class "Default")
      (node (ref "IC5") (pin "7") (pinfunction "7:Y1_7") (pintype "bidirectional"))
      (node (ref "R35") (pin "1") (pinfunction "1_1") (pintype "bidirectional"))
      (node (ref "R37") (pin "2") (pinfunction "2_2") (pintype "bidirectional"))
    )
    (net (code "48") (name "/RC_CH1_ST") (class "Default")
      (node (ref "R34") (pin "2") (pinfunction "2_2") (pintype "bidirectional"))
      (node (ref "ST") (pin "1") (pinfunction "1_1") (pintype "bidirectional"))
    )
    (net (code "49") (name "/RC_CH2_TH") (class "Default")
      (node (ref "R35") (pin "2") (pinfunction "2_2") (pintype "bidirectional"))
      (node (ref "TH") (pin "1") (pinfunction "1_1") (pintype "bidirectional"))
    )
    (net (code "50") (name "/RECV_CH1") (class "Default")
      (node (ref "IC5") (pin "3") (pinfunction "3:B0_3") (pintype "bidirectional"))
      (node (ref "R25") (pin "2") (pinfunction "2_2") (pintype "bidirectional"))
    )
    (net (code "51") (name "/RECV_CH1_H") (class "Default")
      (node (ref "R13") (pin "2") (pinfunction "2_2") (pintype "bidirectional"))
      (node (ref "R15") (pin "1") (pinfunction "1_1") (pintype "bidirectional"))
      (node (ref "R25") (pin "1") (pinfunction "1_1") (pintype "bidirectional"))
    )
    (net (code "52") (name "/RECV_CH2") (class "Default")
      (node (ref "IC5") (pin "6") (pinfunction "6:B1_6") (pintype "bidirectional"))
      (node (ref "R26") (pin "2") (pinfunction "2_2") (pintype "bidirectional"))
    )
    (net (code "53") (name "/RECV_CH2_H") (class "Default")
      (node (ref "R14") (pin "2") (pinfunction "2_2") (pintype "bidirectional"))
      (node (ref "R16") (pin "1") (pinfunction "1_1") (pintype "bidirectional"))
      (node (ref "R26") (pin "1") (pinfunction "1_1") (pintype "bidirectional"))
    )
    (net (code "54") (name "/RX") (class "Default")
      (node (ref "CON1") (pin "10") (pinfunction "RX_10") (pintype "bidirectional"))
    )
    (net (code "55") (name "/SCK1") (class "Default")
      (node (ref "IC4") (pin "2") (pinfunction "2:A_2") (pintype "input"))
      (node (ref "U5") (pin "9") (pinfunction "PA7_A8_D8_SCK_9") (pintype "bidirectional"))
    )
    (net (code "56") (name "/SCL") (class "Default")
      (node (ref "CON1") (pin "5") (pinfunction "SCL_5") (pintype "bidirectional"))
      (node (ref "I2C0") (pin "SCL") (pinfunction "SCL_SCL") (pintype "bidirectional"))
      (node (ref "IC1") (pin "26") (pinfunction "SCL_26") (pintype "bidirectional"))
      (node (ref "R5") (pin "1") (pinfunction "1_1") (pintype "bidirectional"))
      (node (ref "U2") (pin "13") (pinfunction "D0_13") (pintype "bidirectional"))
      (node (ref "U5") (pin "6") (pinfunction "PA9_A5_D5_SCL_6") (pintype "bidirectional"))
    )
    (net (code "57") (name "/SCLK") (class "Default")
      (node (ref "CON1") (pin "23") (pinfunction "SCLK_23") (pintype "bidirectional"))
    )
    (net (code "58") (name "/SDA") (class "Default")
      (node (ref "CON1") (pin "3") (pinfunction "SDA_3") (pintype "bidirectional"))
      (node (ref "I2C0") (pin "SDA") (pinfunction "SDA_SDA") (pintype "bidirectional"))
      (node (ref "IC1") (pin "27") (pinfunction "SDA_27") (pintype "bidirectional"))
      (node (ref "R6") (pin "1") (pinfunction "1_1") (pintype "bidirectional"))
      (node (ref "U2") (pin "11") (pinfunction "D2_11") (pintype "bidirectional"))
      (node (ref "U2") (pin "12") (pinfunction "D1_12") (pintype "bidirectional"))
      (node (ref "U5") (pin "5") (pinfunction "PA8_A4_D4_SDA_5") (pintype "bidirectional"))
    )
    (net (code "59") (name "/SIGNAL_SELCET") (class "Default")
      (node (ref "R41") (pin "1") (pinfunction "1_1") (pintype "bidirectional"))
      (node (ref "T5") (pin "B") (pinfunction "B_B") (pintype "passive"))
      (node (ref "U5") (pin "4") (pinfunction "PA11_A3_D3_4") (pintype "bidirectional"))
    )
    (net (code "60") (name "/TX") (class "Default")
      (node (ref "CON1") (pin "8") (pinfunction "TX_8") (pintype "bidirectional"))
    )
    (net (code "61") (name "/XIAO3V3") (class "Default")
      (node (ref "U5") (pin "12") (pinfunction "3V3_12") (pintype "bidirectional"))
    )
    (net (code "62") (name "/XIAO_RX") (class "Default")
      (node (ref "U5") (pin "8") (pinfunction "PB09_A7_D7_RX_8") (pintype "bidirectional"))
    )
    (net (code "63") (name "/XIAO_TX") (class "Default")
      (node (ref "U5") (pin "7") (pinfunction "PB08_A6_D6_TX_7") (pintype "bidirectional"))
    )
    (net (code "64") (name "3V3_JETSON") (class "Default")
      (node (ref "C1") (pin "2") (pinfunction "2_2") (pintype "passive"))
      (node (ref "C11") (pin "2") (pinfunction "2_2") (pintype "passive"))
      (node (ref "C12") (pin "2") (pinfunction "2_2") (pintype "passive"))
      (node (ref "C2") (pin "2") (pinfunction "2_2") (pintype "passive"))
      (node (ref "C6") (pin "2") (pinfunction "2_2") (pintype "passive"))
      (node (ref "C7") (pin "2") (pinfunction "2_2") (pintype "passive"))
      (node (ref "CON1") (pin "1") (pinfunction "3V3_1") (pintype "bidirectional"))
      (node (ref "CON1") (pin "17") (pinfunction "3V3_17") (pintype "bidirectional"))
      (node (ref "D1") (pin "CATHODE") (pinfunction "CATHODE_CATHODE") (pintype "bidirectional"))
      (node (ref "IC1") (pin "28") (pinfunction "VDD_28") (pintype "bidirectional"))
      (node (ref "R11") (pin "2") (pinfunction "2_2") (pintype "bidirectional"))
      (node (ref "R2") (pin "2") (pinfunction "2_2") (pintype "bidirectional"))
      (node (ref "R5") (pin "2") (pinfunction "2_2") (pintype "bidirectional"))
      (node (ref "R6") (pin "2") (pinfunction "2_2") (pintype "bidirectional"))
      (node (ref "R8") (pin "1") (pinfunction "1_1") (pintype "bidirectional"))
      (node (ref "R9") (pin "1") (pinfunction "1_1") (pintype "bidirectional"))
      (node (ref "U1") (pin "#1") (pinfunction "1:INH_#1") (pintype "bidirectional"))
      (node (ref "U1") (pin "#4") (pinfunction "4:VCC_#4") (pintype "bidirectional"))
      (node (ref "U2") (pin "22") (pinfunction "VDD_22") (pintype "bidirectional"))
      (node (ref "U2") (pin "25") (pinfunction "VBAT_25") (pintype "bidirectional"))
      (node (ref "U3") (pin "8") (pinfunction "8:VDD__8") (pintype "bidirectional"))
      (node (ref "U4") (pin "4") (pinfunction "COL_4") (pintype "passive"))
    )
    (net (code "65") (name "5V") (class "Default")
      (node (ref "C13") (pin "2") (pinfunction "2_2") (pintype "passive"))
      (node (ref "C14") (pin "2") (pinfunction "2_2") (pintype "passive"))
      (node (ref "C15") (pin "2") (pinfunction "2_2") (pintype "passive"))
      (node (ref "CON1") (pin "2") (pinfunction "5V_2") (pintype "bidirectional"))
      (node (ref "D3") (pin "A") (pinfunction "ANODE_A") (pintype "passive"))
      (node (ref "I2C0") (pin "VCC") (pinfunction "VCC_VCC") (pintype "bidirectional"))
      (node (ref "IC3") (pin "5") (pinfunction "5:VCC_5") (pintype "power_in"))
      (node (ref "IC4") (pin "5") (pinfunction "5:VCC_5") (pintype "power_in"))
      (node (ref "LED1") (pin "VCC") (pinfunction "VCC_VCC") (pintype "bidirectional"))
      (node (ref "R39") (pin "2") (pinfunction "2_2") (pintype "bidirectional"))
      (node (ref "SPI-LED") (pin "VCC") (pinfunction "VCC_VCC") (pintype "bidirectional"))
    )
    (net (code "66") (name "5VL_JETSON") (class "Default")
      (node (ref "D3") (pin "K") (pinfunction "CATHODE_K") (pintype "passive"))
      (node (ref "U5") (pin "14") (pinfunction "5V_14") (pintype "bidirectional"))
    )
    (net (code "67") (name "BEC_62") (class "Default")
      (node (ref "CH1") (pin "2") (pinfunction "2_2") (pintype "power_in"))
      (node (ref "CH2") (pin "2") (pinfunction "2_2") (pintype "power_in"))
      (node (ref "CH3") (pin "2") (pinfunction "2_2") (pintype "power_in"))
      (node (ref "D2") (pin "A") (pinfunction "ANODE_A") (pintype "bidirectional"))
      (node (ref "R19") (pin "2") (pinfunction "2_2") (pintype "bidirectional"))
      (node (ref "R20") (pin "2") (pinfunction "2_2") (pintype "bidirectional"))
      (node (ref "RC") (pin "ANODE") (pinfunction "ANODE_ANODE") (pintype "passive"))
      (node (ref "ST") (pin "2") (pinfunction "2_2") (pintype "power_in"))
      (node (ref "TH") (pin "2") (pinfunction "2_2") (pintype "power_in"))
      (node (ref "U4") (pin "1") (pinfunction "A_1") (pintype "passive"))
    )
    (net (code "68") (name "GND") (class "Default")
      (node (ref "C1") (pin "1") (pinfunction "1_1") (pintype "passive"))
      (node (ref "C10") (pin "1") (pinfunction "1_1") (pintype "passive"))
      (node (ref "C11") (pin "1") (pinfunction "1_1") (pintype "passive"))
      (node (ref "C12") (pin "1") (pinfunction "1_1") (pintype "passive"))
      (node (ref "C13") (pin "1") (pinfunction "1_1") (pintype "passive"))
      (node (ref "C14") (pin "1") (pinfunction "1_1") (pintype "passive"))
      (node (ref "C15") (pin "1") (pinfunction "1_1") (pintype "passive"))
      (node (ref "C16") (pin "1") (pinfunction "1_1") (pintype "passive"))
      (node (ref "C17") (pin "1") (pinfunction "1_1") (pintype "passive"))
      (node (ref "C18") (pin "1") (pinfunction "1_1") (pintype "passive"))
      (node (ref "C19") (pin "1") (pinfunction "1_1") (pintype "passive"))
      (node (ref "C2") (pin "1") (pinfunction "1_1") (pintype "passive"))
      (node (ref "C3") (pin "1") (pinfunction "1_1") (pintype "passive"))
      (node (ref "C6") (pin "1") (pinfunction "1_1") (pintype "passive"))
      (node (ref "C7") (pin "1") (pinfunction "1_1") (pintype "passive"))
      (node (ref "C8") (pin "1") (pinfunction "1_1") (pintype "passive"))
      (node (ref "C9") (pin "1") (pinfunction "1_1") (pintype "passive"))
      (node (ref "CH1") (pin "3") (pinfunction "3_3") (pintype "power_in"))
      (node (ref "CH2") (pin "3") (pinfunction "3_3") (pintype "power_in"))
      (node (ref "CH3") (pin "3") (pinfunction "3_3") (pintype "power_in"))
      (node (ref "CON1") (pin "14") (pinfunction "GND_14") (pintype "bidirectional"))
      (node (ref "CON1") (pin "20") (pinfunction "GND_20") (pintype "bidirectional"))
      (node (ref "CON1") (pin "25") (pinfunction "GND_25") (pintype "bidirectional"))
      (node (ref "CON1") (pin "30") (pinfunction "GND_30") (pintype "bidirectional"))
      (node (ref "CON1") (pin "34") (pinfunction "GND_34") (pintype "bidirectional"))
      (node (ref "CON1") (pin "39") (pinfunction "GND_39") (pintype "bidirectional"))
      (node (ref "CON1") (pin "9") (pinfunction "GND_9") (pintype "bidirectional"))
      (node (ref "I2C0") (pin "GND") (pinfunction "GND_GND") (pintype "bidirectional"))
      (node (ref "IC1") (pin "1") (pinfunction "A0_1") (pintype "bidirectional"))
      (node (ref "IC1") (pin "14") (pinfunction "VSS_14") (pintype "bidirectional"))
      (node (ref "IC1") (pin "2") (pinfunction "A1_2") (pintype "bidirectional"))
      (node (ref "IC1") (pin "24") (pinfunction "A5_24") (pintype "bidirectional"))
      (node (ref "IC1") (pin "3") (pinfunction "A2_3") (pintype "bidirectional"))
      (node (ref "IC1") (pin "4") (pinfunction "A3_4") (pintype "bidirectional"))
      (node (ref "IC1") (pin "5") (pinfunction "A4_5") (pintype "bidirectional"))
      (node (ref "IC3") (pin "1") (pinfunction "1:OE_1") (pintype "input"))
      (node (ref "IC3") (pin "3") (pinfunction "3:GND_3") (pintype "power_in"))
      (node (ref "IC4") (pin "1") (pinfunction "1:OE_1") (pintype "input"))
      (node (ref "IC4") (pin "3") (pinfunction "3:GND_3") (pintype "power_in"))
      (node (ref "IC5") (pin "15") (pinfunction "15:E_15") (pintype "bidirectional"))
      (node (ref "IC5") (pin "8") (pinfunction "8:GND_8") (pintype "bidirectional"))
      (node (ref "IC6") (pin "2") (pinfunction "GND_2") (pintype "power_in"))
      (node (ref "LED1") (pin "GND") (pinfunction "GND_GND") (pintype "bidirectional"))
      (node (ref "R1") (pin "1") (pinfunction "1_1") (pintype "bidirectional"))
      (node (ref "R12") (pin "1") (pinfunction "1_1") (pintype "bidirectional"))
      (node (ref "R17") (pin "2") (pinfunction "2_2") (pintype "bidirectional"))
      (node (ref "R18") (pin "2") (pinfunction "2_2") (pintype "bidirectional"))
      (node (ref "R22") (pin "2") (pinfunction "2_2") (pintype "bidirectional"))
      (node (ref "R24") (pin "2") (pinfunction "2_2") (pintype "bidirectional"))
      (node (ref "R27") (pin "1") (pinfunction "1_1") (pintype "bidirectional"))
      (node (ref "R28") (pin "2") (pinfunction "2_2") (pintype "bidirectional"))
      (node (ref "R29") (pin "2") (pinfunction "2_2") (pintype "bidirectional"))
      (node (ref "R30") (pin "2") (pinfunction "2_2") (pintype "bidirectional"))
      (node (ref "R31") (pin "2") (pinfunction "2_2") (pintype "bidirectional"))
      (node (ref "R32") (pin "2") (pinfunction "2_2") (pintype "bidirectional"))
      (node (ref "R33") (pin "2") (pinfunction "2_2") (pintype "bidirectional"))
      (node (ref "R36") (pin "1") (pinfunction "1_1") (pintype "bidirectional"))
      (node (ref "R37") (pin "1") (pinfunction "1_1") (pintype "bidirectional"))
      (node (ref "R39") (pin "1") (pinfunction "1_1") (pintype "bidirectional"))
      (node (ref "R40") (pin "1") (pinfunction "1_1") (pintype "bidirectional"))
      (node (ref "R7") (pin "2") (pinfunction "2_2") (pintype "bidirectional"))
      (node (ref "SPI-LED") (pin "GND") (pinfunction "GND_GND") (pintype "bidirectional"))
      (node (ref "ST") (pin "3") (pinfunction "3_3") (pintype "power_in"))
      (node (ref "T1") (pin "S") (pinfunction "S_S") (pintype "passive"))
      (node (ref "T2") (pin "S") (pinfunction "S_S") (pintype "passive"))
      (node (ref "T3") (pin "S") (pinfunction "S_S") (pintype "passive"))
      (node (ref "T4") (pin "E") (pinfunction "E_E") (pintype "passive"))
      (node (ref "T5") (pin "E") (pinfunction "E_E") (pintype "passive"))
      (node (ref "TH") (pin "3") (pinfunction "3_3") (pintype "power_in"))
      (node (ref "U1") (pin "#2") (pinfunction "2:CASE_GND_#2") (pintype "bidirectional"))
      (node (ref "U2") (pin "10") (pinfunction "D3_10") (pintype "bidirectional"))
      (node (ref "U2") (pin "14") (pinfunction "E/RD#_14") (pintype "bidirectional"))
      (node (ref "U2") (pin "15") (pinfunction "R/W#_15") (pintype "bidirectional"))
      (node (ref "U2") (pin "18") (pinfunction "CS#_18") (pintype "bidirectional"))
      (node (ref "U2") (pin "19") (pinfunction "BS2_19") (pintype "bidirectional"))
      (node (ref "U2") (pin "2") (pinfunction "VLSS_2") (pintype "bidirectional"))
      (node (ref "U2") (pin "21") (pinfunction "BS0_21") (pintype "bidirectional"))
      (node (ref "U2") (pin "23") (pinfunction "VSS_23") (pintype "bidirectional"))
      (node (ref "U2") (pin "6") (pinfunction "D7_6") (pintype "bidirectional"))
      (node (ref "U2") (pin "7") (pinfunction "D6_7") (pintype "bidirectional"))
      (node (ref "U2") (pin "8") (pinfunction "D5_8") (pintype "bidirectional"))
      (node (ref "U2") (pin "9") (pinfunction "D4_9") (pintype "bidirectional"))
      (node (ref "U3") (pin "5") (pinfunction "5:GND_5") (pintype "bidirectional"))
      (node (ref "U5") (pin "13") (pinfunction "GND_13") (pintype "bidirectional"))
    )
    (net (code "69") (name "Net-(C10-Pad2)") (class "Default")
      (node (ref "C10") (pin "2") (pinfunction "2_2") (pintype "passive"))
      (node (ref "D1") (pin "ANODE") (pinfunction "ANODE_ANODE") (pintype "bidirectional"))
      (node (ref "R10") (pin "1") (pinfunction "1_1") (pintype "bidirectional"))
      (node (ref "R9") (pin "2") (pinfunction "2_2") (pintype "bidirectional"))
    )
    (net (code "70") (name "Net-(IC5-9:Y2)") (class "Default")
      (node (ref "IC5") (pin "9") (pinfunction "9:Y2_9") (pintype "bidirectional"))
      (node (ref "R33") (pin "1") (pinfunction "1_1") (pintype "bidirectional"))
    )
    (net (code "71") (name "Net-(IC5-10:B2)") (class "Default")
      (node (ref "IC5") (pin "10") (pinfunction "10:B2_10") (pintype "bidirectional"))
      (node (ref "R32") (pin "1") (pinfunction "1_1") (pintype "bidirectional"))
    )
    (net (code "72") (name "Net-(IC5-11:A2)") (class "Default")
      (node (ref "IC5") (pin "11") (pinfunction "11:A2_11") (pintype "bidirectional"))
      (node (ref "R31") (pin "1") (pinfunction "1_1") (pintype "bidirectional"))
    )
    (net (code "73") (name "Net-(IC5-12:Y3)") (class "Default")
      (node (ref "IC5") (pin "12") (pinfunction "12:Y3_12") (pintype "bidirectional"))
      (node (ref "R30") (pin "1") (pinfunction "1_1") (pintype "bidirectional"))
    )
    (net (code "74") (name "Net-(IC5-13:B3)") (class "Default")
      (node (ref "IC5") (pin "13") (pinfunction "13:B3_13") (pintype "bidirectional"))
      (node (ref "R29") (pin "1") (pinfunction "1_1") (pintype "bidirectional"))
    )
    (net (code "75") (name "Net-(IC5-14:A3)") (class "Default")
      (node (ref "IC5") (pin "14") (pinfunction "14:A3_14") (pintype "bidirectional"))
      (node (ref "R28") (pin "1") (pinfunction "1_1") (pintype "bidirectional"))
    )
    (net (code "76") (name "Net-(IC6-BYPASS)") (class "Default")
      (node (ref "C17") (pin "2") (pinfunction "2_2") (pintype "passive"))
      (node (ref "IC6") (pin "4") (pinfunction "BYPASS_4") (pintype "bidirectional"))
    )
    (net (code "77") (name "Net-(R15-Pad2)") (class "Default")
      (node (ref "R15") (pin "2") (pinfunction "2_2") (pintype "bidirectional"))
      (node (ref "R17") (pin "1") (pinfunction "1_1") (pintype "bidirectional"))
      (node (ref "T1") (pin "G") (pinfunction "G_G") (pintype "passive"))
    )
    (net (code "78") (name "Net-(R16-Pad2)") (class "Default")
      (node (ref "R16") (pin "2") (pinfunction "2_2") (pintype "bidirectional"))
      (node (ref "R18") (pin "1") (pinfunction "1_1") (pintype "bidirectional"))
      (node (ref "T2") (pin "G") (pinfunction "G_G") (pintype "passive"))
    )
    (net (code "79") (name "Net-(R21-Pad2)") (class "Default")
      (node (ref "R21") (pin "2") (pinfunction "2_2") (pintype "bidirectional"))
      (node (ref "T3") (pin "D") (pinfunction "D_D") (pintype "passive"))
    )
    (net (code "80") (name "Net-(R23-Pad1)") (class "Default")
      (node (ref "R23") (pin "1") (pinfunction "1_1") (pintype "bidirectional"))
      (node (ref "R24") (pin "1") (pinfunction "1_1") (pintype "bidirectional"))
      (node (ref "T3") (pin "G") (pinfunction "G_G") (pintype "passive"))
    )
    (net (code "81") (name "Net-(R27-Pad2)") (class "Default")
      (node (ref "R27") (pin "2") (pinfunction "2_2") (pintype "bidirectional"))
      (node (ref "RC") (pin "CATHODE") (pinfunction "CATHODE_CATHODE") (pintype "passive"))
    )
    (net (code "82") (name "Net-(U2-BS1)") (class "Default")
      (node (ref "R8") (pin "2") (pinfunction "2_2") (pintype "bidirectional"))
      (node (ref "U2") (pin "20") (pinfunction "BS1_20") (pintype "bidirectional"))
    )
    (net (code "83") (name "Net-(U2-C1N)") (class "Default")
      (node (ref "C4") (pin "1") (pinfunction "1_1") (pintype "passive"))
      (node (ref "U2") (pin "26") (pinfunction "C1N_26") (pintype "bidirectional"))
    )
    (net (code "84") (name "Net-(U2-C1P)") (class "Default")
      (node (ref "C4") (pin "2") (pinfunction "2_2") (pintype "passive"))
      (node (ref "U2") (pin "27") (pinfunction "C1P_27") (pintype "bidirectional"))
    )
    (net (code "85") (name "Net-(U2-C2N)") (class "Default")
      (node (ref "C5") (pin "1") (pinfunction "1_1") (pintype "passive"))
      (node (ref "U2") (pin "28") (pinfunction "C2N_28") (pintype "bidirectional"))
    )
    (net (code "86") (name "Net-(U2-C2P)") (class "Default")
      (node (ref "C5") (pin "2") (pinfunction "2_2") (pintype "passive"))
      (node (ref "U2") (pin "29") (pinfunction "C2P_29") (pintype "bidirectional"))
    )
    (net (code "87") (name "Net-(U2-D{slash}C#)") (class "Default")
      (node (ref "R11") (pin "1") (pinfunction "1_1") (pintype "bidirectional"))
      (node (ref "R12") (pin "2") (pinfunction "2_2") (pintype "bidirectional"))
      (node (ref "U2") (pin "16") (pinfunction "D/C#_16") (pintype "bidirectional"))
    )
    (net (code "88") (name "Net-(U2-IREF)") (class "Default")
      (node (ref "R7") (pin "1") (pinfunction "1_1") (pintype "bidirectional"))
      (node (ref "U2") (pin "5") (pinfunction "IREF_5") (pintype "bidirectional"))
    )
    (net (code "89") (name "Net-(U2-RES#)") (class "Default")
      (node (ref "R10") (pin "2") (pinfunction "2_2") (pintype "bidirectional"))
      (node (ref "U2") (pin "17") (pinfunction "RES#_17") (pintype "bidirectional"))
    )
    (net (code "90") (name "Net-(U2-VCC)") (class "Default")
      (node (ref "C9") (pin "2") (pinfunction "2_2") (pintype "passive"))
      (node (ref "U2") (pin "3") (pinfunction "VCC_3") (pintype "bidirectional"))
    )
    (net (code "91") (name "Net-(U2-VCOMH)") (class "Default")
      (node (ref "C8") (pin "2") (pinfunction "2_2") (pintype "passive"))
      (node (ref "U2") (pin "4") (pinfunction "VCOMH_4") (pintype "bidirectional"))
    )
    (net (code "92") (name "Net-(U3-1:AN1)") (class "Default")
      (node (ref "R19") (pin "1") (pinfunction "1_1") (pintype "bidirectional"))
      (node (ref "U3") (pin "1") (pinfunction "1:AN1_1") (pintype "bidirectional"))
    )
    (net (code "93") (name "Net-(U3-2:CA1)") (class "Default")
      (node (ref "T1") (pin "D") (pinfunction "D_D") (pintype "passive"))
      (node (ref "U3") (pin "2") (pinfunction "2:CA1_2") (pintype "bidirectional"))
    )
    (net (code "94") (name "Net-(U3-3:CA2)") (class "Default")
      (node (ref "T2") (pin "D") (pinfunction "D_D") (pintype "passive"))
      (node (ref "U3") (pin "3") (pinfunction "3:CA2_3") (pintype "bidirectional"))
    )
    (net (code "95") (name "Net-(U3-4:AN2)") (class "Default")
      (node (ref "R20") (pin "1") (pinfunction "1_1") (pintype "bidirectional"))
      (node (ref "U3") (pin "4") (pinfunction "4:AN2_4") (pintype "bidirectional"))
    )
    (net (code "96") (name "Net-(U4-C)") (class "Default")
      (node (ref "R21") (pin "1") (pinfunction "1_1") (pintype "bidirectional"))
      (node (ref "U4") (pin "2") (pinfunction "C_2") (pintype "passive"))
    )
    (net (code "97") (name "unconnected-(CON1-CE1-Pad26)") (class "Default")
      (node (ref "CON1") (pin "26") (pinfunction "CE1_26") (pintype "bidirectional"))
    )
    (net (code "98") (name "unconnected-(CON1-ID_SC-Pad27)") (class "Default")
      (node (ref "CON1") (pin "27") (pinfunction "ID_SC_27") (pintype "bidirectional"))
    )
    (net (code "99") (name "unconnected-(CON1-ID_SD-Pad28)") (class "Default")
      (node (ref "CON1") (pin "28") (pinfunction "ID_SD_28") (pintype "bidirectional"))
    )
    (net (code "100") (name "unconnected-(IC1-LED2-Pad8)") (class "Default")
      (node (ref "IC1") (pin "8") (pinfunction "LED2_8") (pintype "bidirectional"))
    )
    (net (code "101") (name "unconnected-(IC1-LED3-Pad9)") (class "Default")
      (node (ref "IC1") (pin "9") (pinfunction "LED3_9") (pintype "bidirectional"))
    )
    (net (code "102") (name "unconnected-(IC1-LED4-Pad10)") (class "Default")
      (node (ref "IC1") (pin "10") (pinfunction "LED4_10") (pintype "bidirectional"))
    )
    (net (code "103") (name "unconnected-(IC1-LED5-Pad11)") (class "Default")
      (node (ref "IC1") (pin "11") (pinfunction "LED5_11") (pintype "bidirectional"))
    )
    (net (code "104") (name "unconnected-(IC1-LED6-Pad12)") (class "Default")
      (node (ref "IC1") (pin "12") (pinfunction "LED6_12") (pintype "bidirectional"))
    )
    (net (code "105") (name "unconnected-(IC1-LED7-Pad13)") (class "Default")
      (node (ref "IC1") (pin "13") (pinfunction "LED7_13") (pintype "bidirectional"))
    )
    (net (code "106") (name "unconnected-(IC1-LED8-Pad15)") (class "Default")
      (node (ref "IC1") (pin "15") (pinfunction "LED8_15") (pintype "bidirectional"))
    )
    (net (code "107") (name "unconnected-(IC1-LED9-Pad16)") (class "Default")
      (node (ref "IC1") (pin "16") (pinfunction "LED9_16") (pintype "bidirectional"))
    )
    (net (code "108") (name "unconnected-(IC1-LED10-Pad17)") (class "Default")
      (node (ref "IC1") (pin "17") (pinfunction "LED10_17") (pintype "bidirectional"))
    )
    (net (code "109") (name "unconnected-(IC1-LED11-Pad18)") (class "Default")
      (node (ref "IC1") (pin "18") (pinfunction "LED11_18") (pintype "bidirectional"))
    )
    (net (code "110") (name "unconnected-(IC1-LED12-Pad19)") (class "Default")
      (node (ref "IC1") (pin "19") (pinfunction "LED12_19") (pintype "bidirectional"))
    )
    (net (code "111") (name "unconnected-(IC1-LED13-Pad20)") (class "Default")
      (node (ref "IC1") (pin "20") (pinfunction "LED13_20") (pintype "bidirectional"))
    )
    (net (code "112") (name "unconnected-(IC1-LED14-Pad21)") (class "Default")
      (node (ref "IC1") (pin "21") (pinfunction "LED14_21") (pintype "bidirectional"))
    )
    (net (code "113") (name "unconnected-(IC1-LED15-Pad22)") (class "Default")
      (node (ref "IC1") (pin "22") (pinfunction "LED15_22") (pintype "bidirectional"))
    )
    (net (code "114") (name "unconnected-(U2-NC-Pad1)") (class "Default")
      (node (ref "U2") (pin "1") (pinfunction "NC_1") (pintype "bidirectional"))
    )
    (net (code "115") (name "unconnected-(U2-NC-Pad24)") (class "Default")
      (node (ref "U2") (pin "24") (pinfunction "NC_24") (pintype "bidirectional"))
    )
    (net (code "116") (name "unconnected-(U2-NC-Pad30)") (class "Default")
      (node (ref "U2") (pin "30") (pinfunction "NC_30") (pintype "bidirectional"))
    )
  )
)
